# Microcontroller.net
KiCad netlist of a schematic drawn in Altium Designer
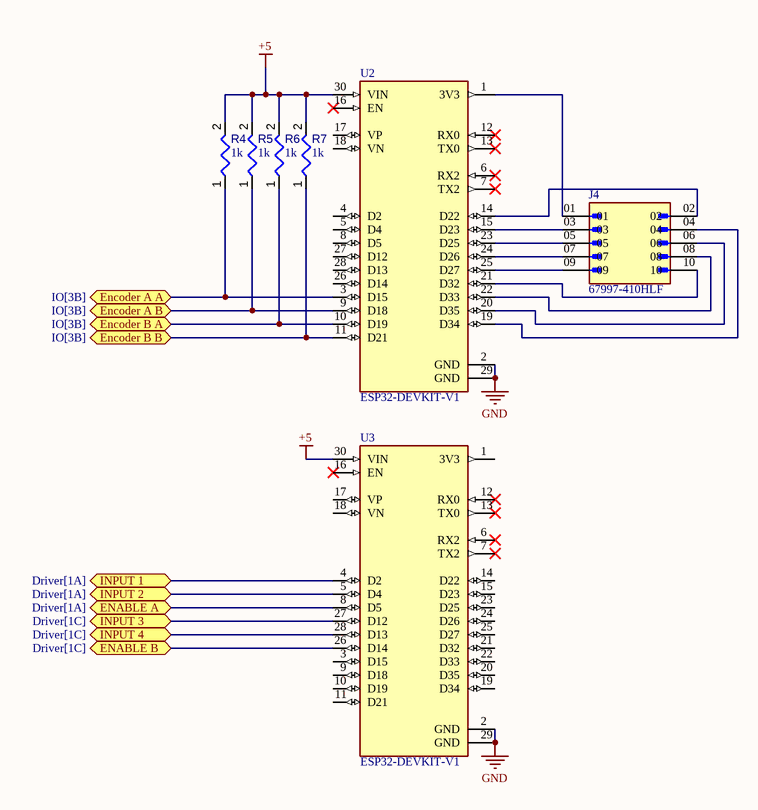
[diagram p0: Microcontroller.SchDoc]

(export (version "E")
  (design (tool "Eeschema 10.0.6"))
  (components
    (comp (ref "J4")
      (value "67997-410HLF")
      (footprint "AMPHENOL_67997-410HLF")
      (fields (field (name "MF") "Amphenol ICC") (field (name "DIGI-KEY_PART_NUMBER") "609-3243-ND"))
      (libsource (lib "NeededParts") (part "67997-410HLF"))
    )
    (comp (ref "R4")
      (value "1k")
      (footprint "RESC1608X55X25ML10T15")
      (description "Chip Resistor, 1 KOhm, +/-1%, 0.1 W, -55 to 155 degC, 0603 (1608 Metric)")
      (fields (field (name "POWER") "100mW") (field (name "TOLERANCE") "1%"))
      (libsource (lib "Ryan Nedjabat") (part "RES-2"))
    )
    (comp (ref "R5")
      (value "1k")
      (footprint "RESC1608X55X25ML10T15")
      (description "Chip Resistor, 1 KOhm, +/-1%, 0.1 W, -55 to 155 degC, 0603 (1608 Metric)")
      (fields (field (name "POWER") "100mW") (field (name "TOLERANCE") "1%"))
      (libsource (lib "Ryan Nedjabat") (part "RES-2"))
    )
    (comp (ref "R6")
      (value "1k")
      (footprint "RESC1608X55X25ML10T15")
      (description "Chip Resistor, 1 KOhm, +/-1%, 0.1 W, -55 to 155 degC, 0603 (1608 Metric)")
      (fields (field (name "POWER") "100mW") (field (name "TOLERANCE") "1%"))
      (libsource (lib "Ryan Nedjabat") (part "RES-2"))
    )
    (comp (ref "R7")
      (value "1k")
      (footprint "RESC1608X55X25ML10T15")
      (description "Chip Resistor, 1 KOhm, +/-1%, 0.1 W, -55 to 155 degC, 0603 (1608 Metric)")
      (fields (field (name "POWER") "100mW") (field (name "TOLERANCE") "1%"))
      (libsource (lib "Ryan Nedjabat") (part "RES-2"))
    )
    (comp (ref "U2")
      (value "ESP32-DEVKIT-V1")
      (footprint "MODULE_ESP32_DEVKIT_V1")
      (fields (field (name "MF") "Do it"))
      (libsource (lib "NeededParts") (part "ESP32-DEVKIT-V1"))
    )
    (comp (ref "U3")
      (value "ESP32-DEVKIT-V1")
      (footprint "MODULE_ESP32_DEVKIT_V1")
      (fields (field (name "MF") "Do it"))
      (libsource (lib "NeededParts") (part "ESP32-DEVKIT-V1"))
    )
  )
  (nets
    (net (code "1") (name "+5") (class "Default")
      (node (ref "R4") (pin "2") (pinfunction "2_2") (pintype "passive"))
      (node (ref "R5") (pin "2") (pinfunction "2_2") (pintype "passive"))
      (node (ref "R6") (pin "2") (pinfunction "2_2") (pintype "passive"))
      (node (ref "R7") (pin "2") (pinfunction "2_2") (pintype "passive"))
      (node (ref "U2") (pin "30") (pinfunction "VIN_30") (pintype "input"))
      (node (ref "U3") (pin "30") (pinfunction "VIN_30") (pintype "input"))
    )
    (net (code "2") (name "/ENABLE A") (class "Default")
      (node (ref "U3") (pin "8") (pinfunction "D5_8") (pintype "bidirectional"))
    )
    (net (code "3") (name "/ENABLE B") (class "Default")
      (node (ref "U3") (pin "26") (pinfunction "D14_26") (pintype "bidirectional"))
    )
    (net (code "4") (name "/Encoder A A") (class "Default")
      (node (ref "R4") (pin "1") (pinfunction "1_1") (pintype "passive"))
      (node (ref "U2") (pin "3") (pinfunction "D15_3") (pintype "bidirectional"))
    )
    (net (code "5") (name "/Encoder A B") (class "Default")
      (node (ref "R5") (pin "1") (pinfunction "1_1") (pintype "passive"))
      (node (ref "U2") (pin "9") (pinfunction "D18_9") (pintype "bidirectional"))
    )
    (net (code "6") (name "/Encoder B A") (class "Default")
      (node (ref "R6") (pin "1") (pinfunction "1_1") (pintype "passive"))
      (node (ref "U2") (pin "10") (pinfunction "D19_10") (pintype "bidirectional"))
    )
    (net (code "7") (name "/Encoder B B") (class "Default")
      (node (ref "R7") (pin "1") (pinfunction "1_1") (pintype "passive"))
      (node (ref "U2") (pin "11") (pinfunction "D21_11") (pintype "bidirectional"))
    )
    (net (code "8") (name "/INPUT 1") (class "Default")
      (node (ref "U3") (pin "4") (pinfunction "D2_4") (pintype "bidirectional"))
    )
    (net (code "9") (name "/INPUT 2") (class "Default")
      (node (ref "U3") (pin "5") (pinfunction "D4_5") (pintype "bidirectional"))
    )
    (net (code "10") (name "/INPUT 3") (class "Default")
      (node (ref "U3") (pin "27") (pinfunction "D12_27") (pintype "bidirectional"))
    )
    (net (code "11") (name "/INPUT 4") (class "Default")
      (node (ref "U3") (pin "28") (pinfunction "D13_28") (pintype "bidirectional"))
    )
    (net (code "12") (name "GND") (class "Default")
      (node (ref "U2") (pin "2") (pinfunction "GND_2") (pintype "power_in"))
      (node (ref "U2") (pin "29") (pinfunction "GND_29") (pintype "power_in"))
      (node (ref "U3") (pin "2") (pinfunction "GND_2") (pintype "power_in"))
      (node (ref "U3") (pin "29") (pinfunction "GND_29") (pintype "power_in"))
    )
    (net (code "13") (name "Net-(U2-3V3)") (class "Default")
      (node (ref "J4") (pin "01") (pinfunction "01_01") (pintype "passive"))
      (node (ref "U2") (pin "1") (pinfunction "3V3_1") (pintype "output"))
    )
    (net (code "14") (name "Net-(U2-D22)") (class "Default")
      (node (ref "J4") (pin "02") (pinfunction "02_02") (pintype "passive"))
      (node (ref "U2") (pin "14") (pinfunction "D22_14") (pintype "bidirectional"))
    )
    (net (code "15") (name "Net-(U2-D23)") (class "Default")
      (node (ref "J4") (pin "03") (pinfunction "03_03") (pintype "passive"))
      (node (ref "U2") (pin "15") (pinfunction "D23_15") (pintype "bidirectional"))
    )
    (net (code "16") (name "Net-(U2-D25)") (class "Default")
      (node (ref "J4") (pin "05") (pinfunction "05_05") (pintype "passive"))
      (node (ref "U2") (pin "23") (pinfunction "D25_23") (pintype "bidirectional"))
    )
    (net (code "17") (name "Net-(U2-D26)") (class "Default")
      (node (ref "J4") (pin "07") (pinfunction "07_07") (pintype "passive"))
      (node (ref "U2") (pin "24") (pinfunction "D26_24") (pintype "bidirectional"))
    )
    (net (code "18") (name "Net-(U2-D27)") (class "Default")
      (node (ref "J4") (pin "09") (pinfunction "09_09") (pintype "passive"))
      (node (ref "U2") (pin "25") (pinfunction "D27_25") (pintype "bidirectional"))
    )
    (net (code "19") (name "Net-(U2-D32)") (class "Default")
      (node (ref "J4") (pin "10") (pinfunction "10_10") (pintype "passive"))
      (node (ref "U2") (pin "21") (pinfunction "D32_21") (pintype "bidirectional"))
    )
    (net (code "20") (name "Net-(U2-D33)") (class "Default")
      (node (ref "J4") (pin "08") (pinfunction "08_08") (pintype "passive"))
      (node (ref "U2") (pin "22") (pinfunction "D33_22") (pintype "bidirectional"))
    )
    (net (code "21") (name "Net-(U2-D34)") (class "Default")
      (node (ref "J4") (pin "04") (pinfunction "04_04") (pintype "passive"))
      (node (ref "U2") (pin "19") (pinfunction "D34_19") (pintype "bidirectional"))
    )
    (net (code "22") (name "Net-(U2-D35)") (class "Default")
      (node (ref "J4") (pin "06") (pinfunction "06_06") (pintype "passive"))
      (node (ref "U2") (pin "20") (pinfunction "D35_20") (pintype "bidirectional"))
    )
    (net (code "23") (name "unconnected-(U2-D2-Pad4)") (class "Default")
      (node (ref "U2") (pin "4") (pinfunction "D2_4") (pintype "bidirectional"))
    )
    (net (code "24") (name "unconnected-(U2-D4-Pad5)") (class "Default")
      (node (ref "U2") (pin "5") (pinfunction "D4_5") (pintype "bidirectional"))
    )
    (net (code "25") (name "unconnected-(U2-D5-Pad8)") (class "Default")
      (node (ref "U2") (pin "8") (pinfunction "D5_8") (pintype "bidirectional"))
    )
    (net (code "26") (name "unconnected-(U2-D12-Pad27)") (class "Default")
      (node (ref "U2") (pin "27") (pinfunction "D12_27") (pintype "bidirectional"))
    )
    (net (code "27") (name "unconnected-(U2-D13-Pad28)") (class "Default")
      (node (ref "U2") (pin "28") (pinfunction "D13_28") (pintype "bidirectional"))
    )
    (net (code "28") (name "unconnected-(U2-D14-Pad26)") (class "Default")
      (node (ref "U2") (pin "26") (pinfunction "D14_26") (pintype "bidirectional"))
    )
    (net (code "29") (name "unconnected-(U2-EN-Pad16)") (class "Default")
      (node (ref "U2") (pin "16") (pinfunction "EN_16") (pintype "input+no_connect"))
    )
    (net (code "30") (name "unconnected-(U2-RX0-Pad12)") (class "Default")
      (node (ref "U2") (pin "12") (pinfunction "RX0_12") (pintype "input+no_connect"))
    )
    (net (code "31") (name "unconnected-(U2-RX2-Pad6)") (class "Default")
      (node (ref "U2") (pin "6") (pinfunction "RX2_6") (pintype "input+no_connect"))
    )
    (net (code "32") (name "unconnected-(U2-TX0-Pad13)") (class "Default")
      (node (ref "U2") (pin "13") (pinfunction "TX0_13") (pintype "output+no_connect"))
    )
    (net (code "33") (name "unconnected-(U2-TX2-Pad7)") (class "Default")
      (node (ref "U2") (pin "7") (pinfunction "TX2_7") (pintype "output+no_connect"))
    )
    (net (code "34") (name "unconnected-(U2-VN-Pad18)") (class "Default")
      (node (ref "U2") (pin "18") (pinfunction "VN_18") (pintype "bidirectional"))
    )
    (net (code "35") (name "unconnected-(U2-VP-Pad17)") (class "Default")
      (node (ref "U2") (pin "17") (pinfunction "VP_17") (pintype "bidirectional"))
    )
    (net (code "36") (name "unconnected-(U3-3V3-Pad1)") (class "Default")
      (node (ref "U3") (pin "1") (pinfunction "3V3_1") (pintype "output"))
    )
    (net (code "37") (name "unconnected-(U3-D15-Pad3)") (class "Default")
      (node (ref "U3") (pin "3") (pinfunction "D15_3") (pintype "bidirectional"))
    )
    (net (code "38") (name "unconnected-(U3-D18-Pad9)") (class "Default")
      (node (ref "U3") (pin "9") (pinfunction "D18_9") (pintype "bidirectional"))
    )
    (net (code "39") (name "unconnected-(U3-D19-Pad10)") (class "Default")
      (node (ref "U3") (pin "10") (pinfunction "D19_10") (pintype "bidirectional"))
    )
    (net (code "40") (name "unconnected-(U3-D21-Pad11)") (class "Default")
      (node (ref "U3") (pin "11") (pinfunction "D21_11") (pintype "bidirectional"))
    )
    (net (code "41") (name "unconnected-(U3-D22-Pad14)") (class "Default")
      (node (ref "U3") (pin "14") (pinfunction "D22_14") (pintype "bidirectional"))
    )
    (net (code "42") (name "unconnected-(U3-D23-Pad15)") (class "Default")
      (node (ref "U3") (pin "15") (pinfunction "D23_15") (pintype "bidirectional"))
    )
    (net (code "43") (name "unconnected-(U3-D25-Pad23)") (class "Default")
      (node (ref "U3") (pin "23") (pinfunction "D25_23") (pintype "bidirectional"))
    )
    (net (code "44") (name "unconnected-(U3-D26-Pad24)") (class "Default")
      (node (ref "U3") (pin "24") (pinfunction "D26_24") (pintype "bidirectional"))
    )
    (net (code "45") (name "unconnected-(U3-D27-Pad25)") (class "Default")
      (node (ref "U3") (pin "25") (pinfunction "D27_25") (pintype "bidirectional"))
    )
    (net (code "46") (name "unconnected-(U3-D32-Pad21)") (class "Default")
      (node (ref "U3") (pin "21") (pinfunction "D32_21") (pintype "bidirectional"))
    )
    (net (code "47") (name "unconnected-(U3-D33-Pad22)") (class "Default")
      (node (ref "U3") (pin "22") (pinfunction "D33_22") (pintype "bidirectional"))
    )
    (net (code "48") (name "unconnected-(U3-D34-Pad19)") (class "Default")
      (node (ref "U3") (pin "19") (pinfunction "D34_19") (pintype "bidirectional"))
    )
    (net (code "49") (name "unconnected-(U3-D35-Pad20)") (class "Default")
      (node (ref "U3") (pin "20") (pinfunction "D35_20") (pintype "bidirectional"))
    )
    (net (code "50") (name "unconnected-(U3-EN-Pad16)") (class "Default")
      (node (ref "U3") (pin "16") (pinfunction "EN_16") (pintype "input+no_connect"))
    )
    (net (code "51") (name "unconnected-(U3-RX0-Pad12)") (class "Default")
      (node (ref "U3") (pin "12") (pinfunction "RX0_12") (pintype "input+no_connect"))
    )
    (net (code "52") (name "unconnected-(U3-RX2-Pad6)") (class "Default")
      (node (ref "U3") (pin "6") (pinfunction "RX2_6") (pintype "input+no_connect"))
    )
    (net (code "53") (name "unconnected-(U3-TX0-Pad13)") (class "Default")
      (node (ref "U3") (pin "13") (pinfunction "TX0_13") (pintype "output+no_connect"))
    )
    (net (code "54") (name "unconnected-(U3-TX2-Pad7)") (class "Default")
      (node (ref "U3") (pin "7") (pinfunction "TX2_7") (pintype "output+no_connect"))
    )
    (net (code "55") (name "unconnected-(U3-VN-Pad18)") (class "Default")
      (node (ref "U3") (pin "18") (pinfunction "VN_18") (pintype "bidirectional"))
    )
    (net (code "56") (name "unconnected-(U3-VP-Pad17)") (class "Default")
      (node (ref "U3") (pin "17") (pinfunction "VP_17") (pintype "bidirectional"))
    )
  )
)
